# SCH_Juzer_pedal_sch_2024-03-11.net
KiCad netlist of a schematic drawn in EasyEDA
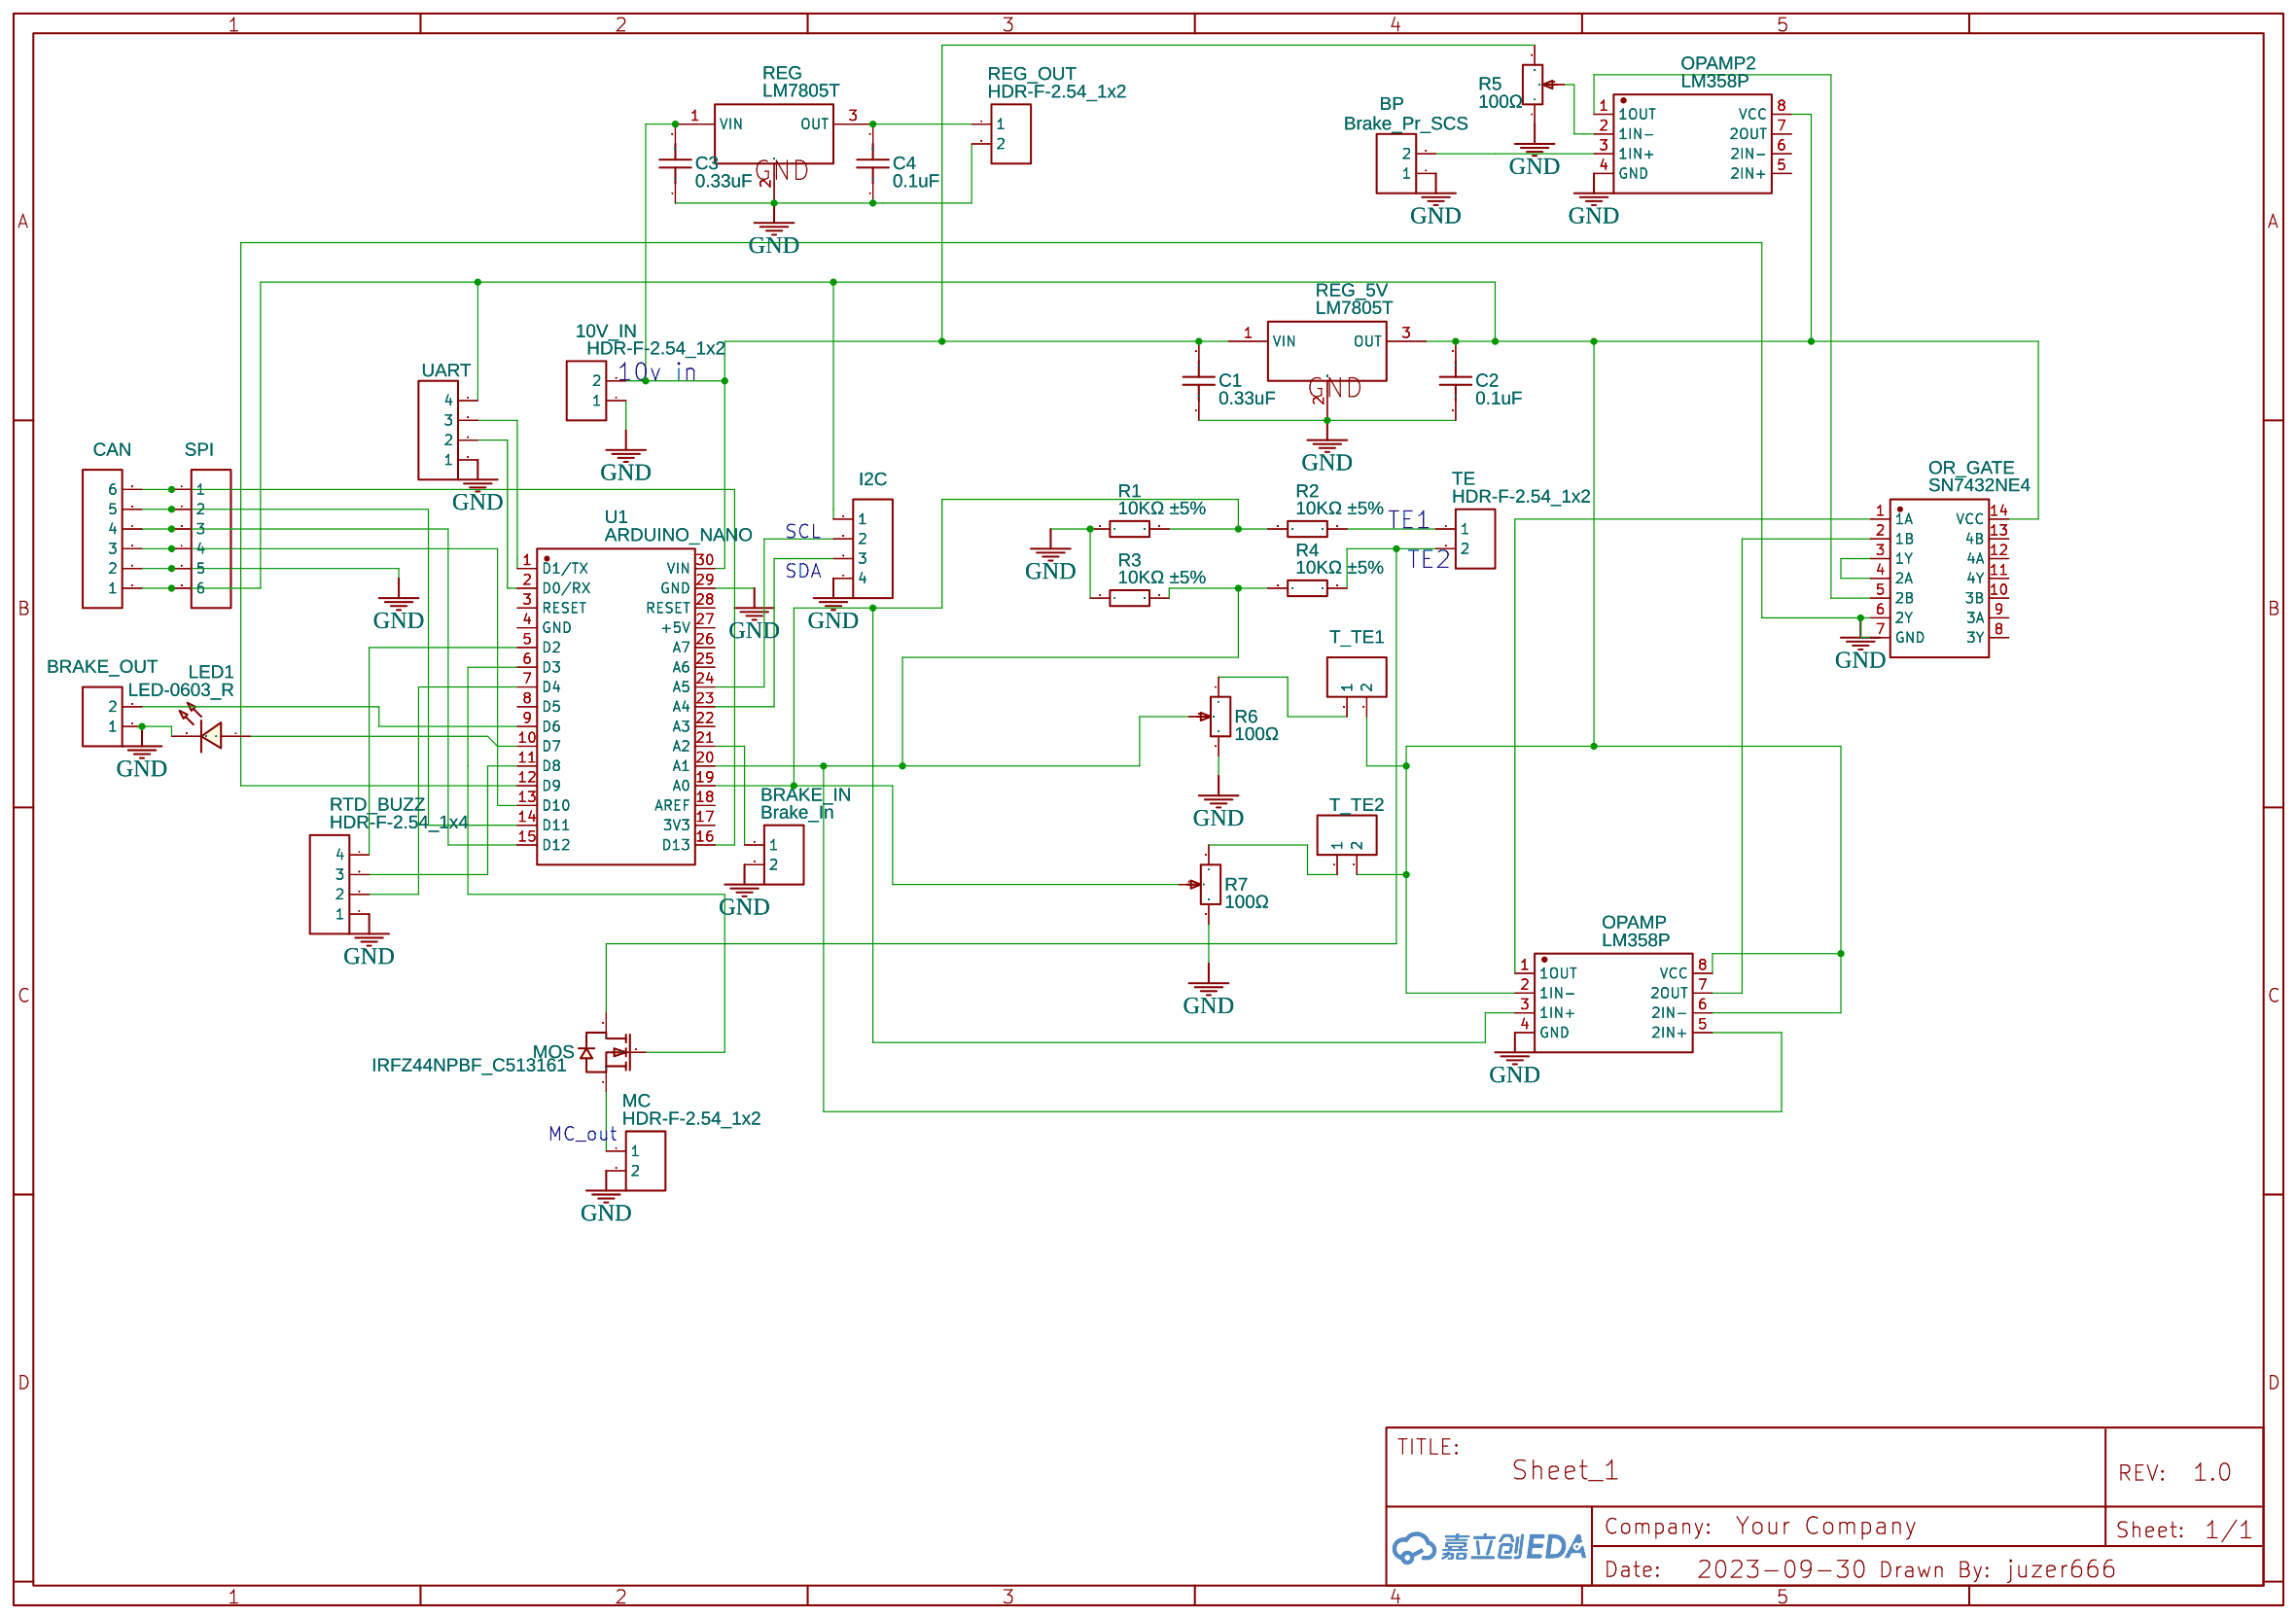
[diagram p0: schematic sheet]

(export (version "E")
  (design (tool "Eeschema 10.0.6"))
  (components
    (comp (ref "10V_IN") (value "HDR-F-2.54_1x2") (libsource (lib "") (part "HDR-F-2.54_1x2_3")))
    (comp (ref "BP") (value "Brake_Pr_SCS") (libsource (lib "") (part "HDR-F-2.54_1x2_2")))
    (comp (ref "BRAKE_IN") (value "Brake_In") (libsource (lib "") (part "HDR-F-2.54_1x2_6")))
    (comp (ref "BRAKE_OUT") (value "Brake_Out") (libsource (lib "") (part "HDR-F-2.54_1x2_4")))
    (comp (ref "C1")
      (value "0.33uF")
      (fields
        (field (name "Manufacturer Part") "250V 0.1UF 5% CBBCapacitor")
        (field (name "Manufacturer") "ReliaPro")
      )
      (libsource (lib "") (part "250V 0.1UF 5% CBBCapacitor"))
    )
    (comp (ref "C2")
      (value "0.1uF")
      (fields
        (field (name "Manufacturer Part") "250V 0.1UF 5% CBBCapacitor")
        (field (name "Manufacturer") "ReliaPro")
      )
      (libsource (lib "") (part "250V 0.1UF 5% CBBCapacitor"))
    )
    (comp (ref "C3")
      (value "0.33uF")
      (fields
        (field (name "Manufacturer Part") "250V 0.1UF 5% CBBCapacitor")
        (field (name "Manufacturer") "ReliaPro")
      )
      (libsource (lib "") (part "250V 0.1UF 5% CBBCapacitor"))
    )
    (comp (ref "C4")
      (value "0.1uF")
      (fields
        (field (name "Manufacturer Part") "250V 0.1UF 5% CBBCapacitor")
        (field (name "Manufacturer") "ReliaPro")
      )
      (libsource (lib "") (part "250V 0.1UF 5% CBBCapacitor"))
    )
    (comp (ref "CAN") (value "CAN") (libsource (lib "") (part "HDR-F-2.54_1x6_1")))
    (comp (ref "I2C") (value "I2C") (libsource (lib "") (part "HDR-F-2.54_1x4")))
    (comp (ref "LED1")
      (value "LED-0603_R")
      (fields
        (field (name "Manufacturer Part") "19-217/R6C-AL1M2VY/3T")
        (field (name "Manufacturer") "EVERLIGHT(台湾亿光)")
      )
      (libsource (lib "") (part "LED-0603_R"))
    )
    (comp (ref "MC") (value "HDR-F-2.54_1x2") (libsource (lib "") (part "HDR-F-2.54_1x2")))
    (comp (ref "MOS")
      (value "IRFZ44NPBF_C513161")
      (fields (field (name "Manufacturer Part") "IRFZ44NPBF"))
      (libsource (lib "") (part "IRFZ44NPBF_C513161"))
    )
    (comp (ref "OPAMP")
      (value "LM358P")
      (fields (field (name "Manufacturer") "TI(德州仪器)"))
      (libsource (lib "") (part "LM358P"))
    )
    (comp (ref "OPAMP2")
      (value "LM358P")
      (fields (field (name "Manufacturer") "TI(德州仪器)"))
      (libsource (lib "") (part "LM358P"))
    )
    (comp (ref "OR_GATE")
      (value "SN7432NE4")
      (fields (field (name "Manufacturer") "TI(德州仪器)"))
      (libsource (lib "") (part "SN7432NE4"))
    )
    (comp (ref "R1")
      (value "10KΩ ±5%")
      (fields
        (field (name "Manufacturer Part") "MF58 103J3470")
        (field (name "Manufacturer") "Nanjing Shiheng Elec")
      )
      (libsource (lib "") (part "RESISTANCE_10K"))
    )
    (comp (ref "R2")
      (value "10KΩ ±5%")
      (fields
        (field (name "Manufacturer Part") "MF58 103J3470")
        (field (name "Manufacturer") "Nanjing Shiheng Elec")
      )
      (libsource (lib "") (part "RESISTANCE_10K"))
    )
    (comp (ref "R3")
      (value "10KΩ ±5%")
      (fields
        (field (name "Manufacturer Part") "MF58 103J3470")
        (field (name "Manufacturer") "Nanjing Shiheng Elec")
      )
      (libsource (lib "") (part "RESISTANCE_10K"))
    )
    (comp (ref "R4")
      (value "10KΩ ±5%")
      (fields
        (field (name "Manufacturer Part") "MF58 103J3470")
        (field (name "Manufacturer") "Nanjing Shiheng Elec")
      )
      (libsource (lib "") (part "RESISTANCE_10K"))
    )
    (comp (ref "R5")
      (value "100Ω")
      (fields (field (name "Manufacturer Part") "3296W-1-101LF") (field (name "Manufacturer") "BOURNS"))
      (libsource (lib "") (part "3296W-1-101LF_1"))
    )
    (comp (ref "R6")
      (value "100Ω")
      (fields (field (name "Manufacturer Part") "3296W-1-101LF") (field (name "Manufacturer") "BOURNS"))
      (libsource (lib "") (part "3296W-1-101LF"))
    )
    (comp (ref "R7")
      (value "100Ω")
      (fields (field (name "Manufacturer Part") "3296W-1-101LF") (field (name "Manufacturer") "BOURNS"))
      (libsource (lib "") (part "3296W-1-101LF"))
    )
    (comp (ref "REG")
      (value "LM7805T")
      (fields (field (name "Manufacturer") "HGC(华冠)"))
      (libsource (lib "") (part "LM7805T_1"))
    )
    (comp (ref "REG_5V")
      (value "LM7805T")
      (fields (field (name "Manufacturer") "HGC(华冠)"))
      (libsource (lib "") (part "LM7805T"))
    )
    (comp (ref "REG_OUT") (value "HDR-F-2.54_1x2") (libsource (lib "") (part "HDR-F-2.54_1x2_1")))
    (comp (ref "RTD_BUZZ") (value "HDR-F-2.54_1x4") (libsource (lib "") (part "HDR-F-2.54_1x4_1")))
    (comp (ref "SPI") (value "SPI") (libsource (lib "") (part "HDR-F-2.54_1x6")))
    (comp (ref "TE") (value "HDR-F-2.54_1x2") (libsource (lib "") (part "HDR-F-2.54_1x2_7")))
    (comp (ref "T_TE1") (value "TE1_Test") (libsource (lib "") (part "HDR-F-2.54_1x2_5")))
    (comp (ref "T_TE2") (value "TE2_Test") (libsource (lib "") (part "HDR-F-2.54_1x2_5")))
    (comp (ref "U1") (value "ARDUINO_NANO") (libsource (lib "") (part "ARDUINO_NANO")))
    (comp (ref "UART") (value "UART") (libsource (lib "") (part "HDR-F-2.54_1x4_2")))
  )
  (nets
    (net (code "1") (name "GND") (class "Default")
      (node (ref "10V_IN") (pin "1") (pinfunction "1_1") (pintype "input"))
      (node (ref "BP") (pin "1") (pinfunction "1_1") (pintype "input"))
      (node (ref "BRAKE_IN") (pin "2") (pinfunction "2_2") (pintype "input"))
      (node (ref "BRAKE_OUT") (pin "1") (pinfunction "1_1") (pintype "input"))
      (node (ref "C1") (pin "1") (pinfunction "1_1") (pintype "unspecified"))
      (node (ref "C2") (pin "1") (pinfunction "1_1") (pintype "unspecified"))
      (node (ref "C3") (pin "1") (pinfunction "1_1") (pintype "unspecified"))
      (node (ref "C4") (pin "1") (pinfunction "1_1") (pintype "unspecified"))
      (node (ref "CAN") (pin "2") (pinfunction "2_2") (pintype "input"))
      (node (ref "I2C") (pin "4") (pinfunction "4_4") (pintype "unspecified"))
      (node (ref "LED1") (pin "2") (pinfunction "2_2") (pintype "unspecified"))
      (node (ref "MC") (pin "2") (pinfunction "2_2") (pintype "input"))
      (node (ref "OPAMP") (pin "4") (pinfunction "GND_4") (pintype "unspecified"))
      (node (ref "OPAMP2") (pin "4") (pinfunction "GND_4") (pintype "unspecified"))
      (node (ref "OR_GATE") (pin "6") (pinfunction "2Y_6") (pintype "unspecified"))
      (node (ref "OR_GATE") (pin "7") (pinfunction "GND_7") (pintype "unspecified"))
      (node (ref "R1") (pin "1") (pinfunction "1_1") (pintype "unspecified"))
      (node (ref "R3") (pin "1") (pinfunction "1_1") (pintype "unspecified"))
      (node (ref "R5") (pin "1") (pinfunction "1_1") (pintype "input"))
      (node (ref "R6") (pin "3") (pinfunction "3_3") (pintype "input"))
      (node (ref "R7") (pin "3") (pinfunction "3_3") (pintype "input"))
      (node (ref "REG") (pin "2") (pinfunction "GND_2") (pintype "passive"))
      (node (ref "REG_5V") (pin "2") (pinfunction "GND_2") (pintype "passive"))
      (node (ref "REG_OUT") (pin "2") (pinfunction "2_2") (pintype "input"))
      (node (ref "RTD_BUZZ") (pin "1") (pinfunction "1_1") (pintype "unspecified"))
      (node (ref "SPI") (pin "5") (pinfunction "5_5") (pintype "input"))
      (node (ref "U1") (pin "12") (pinfunction "D9_12") (pintype "unspecified"))
      (node (ref "U1") (pin "29") (pinfunction "GND_29") (pintype "unspecified"))
      (node (ref "UART") (pin "1") (pinfunction "1_1") (pintype "unspecified"))
    )
    (net (code "2") (name "Net-(MOS-D)") (class "Default")
      (node (ref "MOS") (pin "2") (pinfunction "D_2") (pintype "unspecified"))
      (node (ref "R4") (pin "2") (pinfunction "2_2") (pintype "unspecified"))
      (node (ref "TE") (pin "2") (pinfunction "2_2") (pintype "input"))
    )
    (net (code "3") (name "Net-(MOS-G)") (class "Default")
      (node (ref "MOS") (pin "1") (pinfunction "G_1") (pintype "unspecified"))
      (node (ref "U1") (pin "6") (pinfunction "D3_6") (pintype "unspecified"))
    )
    (net (code "4") (name "Net-(MOS-S)") (class "Default")
      (node (ref "MC") (pin "1") (pinfunction "1_1") (pintype "input"))
      (node (ref "MOS") (pin "3") (pinfunction "S_3") (pintype "unspecified"))
    )
    (net (code "5") (name "Net-(OPAMP-1IN+)") (class "Default")
      (node (ref "OPAMP") (pin "3") (pinfunction "1IN+_3") (pintype "unspecified"))
      (node (ref "R1") (pin "2") (pinfunction "2_2") (pintype "unspecified"))
      (node (ref "R2") (pin "1") (pinfunction "1_1") (pintype "unspecified"))
      (node (ref "R7") (pin "2") (pinfunction "2_2") (pintype "input"))
      (node (ref "U1") (pin "19") (pinfunction "A0_19") (pintype "unspecified"))
    )
    (net (code "6") (name "Net-(OPAMP-1IN-)") (class "Default")
      (node (ref "C2") (pin "2") (pinfunction "2_2") (pintype "unspecified"))
      (node (ref "CAN") (pin "1") (pinfunction "1_1") (pintype "input"))
      (node (ref "I2C") (pin "1") (pinfunction "1_1") (pintype "unspecified"))
      (node (ref "OPAMP") (pin "2") (pinfunction "1IN-_2") (pintype "unspecified"))
      (node (ref "OPAMP") (pin "6") (pinfunction "2IN-_6") (pintype "unspecified"))
      (node (ref "OPAMP") (pin "8") (pinfunction "VCC_8") (pintype "unspecified"))
      (node (ref "OPAMP2") (pin "8") (pinfunction "VCC_8") (pintype "unspecified"))
      (node (ref "OR_GATE") (pin "14") (pinfunction "VCC_14") (pintype "unspecified"))
      (node (ref "REG_5V") (pin "3") (pinfunction "OUT_3") (pintype "passive"))
      (node (ref "SPI") (pin "6") (pinfunction "6_6") (pintype "input"))
      (node (ref "T_TE1") (pin "2") (pinfunction "2_2") (pintype "input"))
      (node (ref "T_TE2") (pin "2") (pinfunction "2_2") (pintype "input"))
      (node (ref "UART") (pin "4") (pinfunction "4_4") (pintype "unspecified"))
    )
    (net (code "7") (name "Net-(OPAMP-1OUT)") (class "Default")
      (node (ref "OPAMP") (pin "1") (pinfunction "1OUT_1") (pintype "unspecified"))
      (node (ref "OR_GATE") (pin "1") (pinfunction "1A_1") (pintype "unspecified"))
    )
    (net (code "8") (name "Net-(OPAMP-2IN+)") (class "Default")
      (node (ref "OPAMP") (pin "5") (pinfunction "2IN+_5") (pintype "unspecified"))
      (node (ref "R3") (pin "2") (pinfunction "2_2") (pintype "unspecified"))
      (node (ref "R4") (pin "1") (pinfunction "1_1") (pintype "unspecified"))
      (node (ref "R6") (pin "2") (pinfunction "2_2") (pintype "input"))
      (node (ref "U1") (pin "20") (pinfunction "A1_20") (pintype "unspecified"))
    )
    (net (code "9") (name "Net-(OPAMP-2OUT)") (class "Default")
      (node (ref "OPAMP") (pin "7") (pinfunction "2OUT_7") (pintype "unspecified"))
      (node (ref "OR_GATE") (pin "2") (pinfunction "1B_2") (pintype "unspecified"))
    )
    (net (code "10") (name "Net-(OPAMP2-1IN+)") (class "Default")
      (node (ref "BP") (pin "2") (pinfunction "2_2") (pintype "input"))
      (node (ref "OPAMP2") (pin "3") (pinfunction "1IN+_3") (pintype "unspecified"))
    )
    (net (code "11") (name "Net-(OPAMP2-1IN-)") (class "Default")
      (node (ref "OPAMP2") (pin "2") (pinfunction "1IN-_2") (pintype "unspecified"))
      (node (ref "R5") (pin "2") (pinfunction "2_2") (pintype "input"))
    )
    (net (code "12") (name "Net-(OPAMP2-1OUT)") (class "Default")
      (node (ref "OPAMP2") (pin "1") (pinfunction "1OUT_1") (pintype "unspecified"))
      (node (ref "OR_GATE") (pin "5") (pinfunction "2B_5") (pintype "unspecified"))
    )
    (net (code "13") (name "Net-(OR_GATE-1Y)") (class "Default")
      (node (ref "OR_GATE") (pin "3") (pinfunction "1Y_3") (pintype "unspecified"))
      (node (ref "OR_GATE") (pin "4") (pinfunction "2A_4") (pintype "unspecified"))
    )
    (net (code "14") (name "Net-(R2-Pad2)") (class "Default")
      (node (ref "R2") (pin "2") (pinfunction "2_2") (pintype "unspecified"))
      (node (ref "TE") (pin "1") (pinfunction "1_1") (pintype "input"))
    )
    (net (code "15") (name "Net-(R6-Pad1)") (class "Default")
      (node (ref "R6") (pin "1") (pinfunction "1_1") (pintype "input"))
      (node (ref "T_TE1") (pin "1") (pinfunction "1_1") (pintype "input"))
    )
    (net (code "16") (name "Net-(R7-Pad1)") (class "Default")
      (node (ref "R7") (pin "1") (pinfunction "1_1") (pintype "input"))
      (node (ref "T_TE2") (pin "1") (pinfunction "1_1") (pintype "input"))
    )
    (net (code "17") (name "Net-(REG-OUT)") (class "Default")
      (node (ref "C4") (pin "2") (pinfunction "2_2") (pintype "unspecified"))
      (node (ref "REG") (pin "3") (pinfunction "OUT_3") (pintype "passive"))
      (node (ref "REG_OUT") (pin "1") (pinfunction "1_1") (pintype "input"))
    )
    (net (code "18") (name "Net-(REG-VIN)") (class "Default")
      (node (ref "10V_IN") (pin "2") (pinfunction "2_2") (pintype "input"))
      (node (ref "C1") (pin "2") (pinfunction "2_2") (pintype "unspecified"))
      (node (ref "C3") (pin "2") (pinfunction "2_2") (pintype "unspecified"))
      (node (ref "R5") (pin "3") (pinfunction "3_3") (pintype "input"))
      (node (ref "REG") (pin "1") (pinfunction "VIN_1") (pintype "passive"))
      (node (ref "REG_5V") (pin "1") (pinfunction "VIN_1") (pintype "passive"))
      (node (ref "U1") (pin "30") (pinfunction "VIN_30") (pintype "unspecified"))
    )
    (net (code "19") (name "Net-(U1-A2)") (class "Default")
      (node (ref "BRAKE_IN") (pin "1") (pinfunction "1_1") (pintype "input"))
      (node (ref "U1") (pin "21") (pinfunction "A2_21") (pintype "unspecified"))
    )
    (net (code "20") (name "Net-(U1-A4)") (class "Default")
      (node (ref "I2C") (pin "3") (pinfunction "3_3") (pintype "unspecified"))
      (node (ref "U1") (pin "23") (pinfunction "A4_23") (pintype "unspecified"))
    )
    (net (code "21") (name "Net-(U1-A5)") (class "Default")
      (node (ref "I2C") (pin "2") (pinfunction "2_2") (pintype "unspecified"))
      (node (ref "U1") (pin "24") (pinfunction "A5_24") (pintype "unspecified"))
    )
    (net (code "22") (name "Net-(U1-D0{slash}RX)") (class "Default")
      (node (ref "U1") (pin "2") (pinfunction "D0/RX_2") (pintype "unspecified"))
      (node (ref "UART") (pin "2") (pinfunction "2_2") (pintype "unspecified"))
    )
    (net (code "23") (name "Net-(U1-D1{slash}TX)") (class "Default")
      (node (ref "U1") (pin "1") (pinfunction "D1/TX_1") (pintype "unspecified"))
      (node (ref "UART") (pin "3") (pinfunction "3_3") (pintype "unspecified"))
    )
    (net (code "24") (name "Net-(U1-D2)") (class "Default")
      (node (ref "RTD_BUZZ") (pin "4") (pinfunction "4_4") (pintype "unspecified"))
      (node (ref "U1") (pin "5") (pinfunction "D2_5") (pintype "unspecified"))
    )
    (net (code "25") (name "Net-(U1-D4)") (class "Default")
      (node (ref "RTD_BUZZ") (pin "2") (pinfunction "2_2") (pintype "unspecified"))
      (node (ref "U1") (pin "7") (pinfunction "D4_7") (pintype "unspecified"))
    )
    (net (code "26") (name "Net-(U1-D6)") (class "Default")
      (node (ref "BRAKE_OUT") (pin "2") (pinfunction "2_2") (pintype "input"))
      (node (ref "U1") (pin "9") (pinfunction "D6_9") (pintype "unspecified"))
    )
    (net (code "27") (name "Net-(U1-D7)") (class "Default")
      (node (ref "LED1") (pin "1") (pinfunction "1_1") (pintype "unspecified"))
      (node (ref "U1") (pin "10") (pinfunction "D7_10") (pintype "unspecified"))
    )
    (net (code "28") (name "Net-(U1-D8)") (class "Default")
      (node (ref "RTD_BUZZ") (pin "3") (pinfunction "3_3") (pintype "unspecified"))
      (node (ref "U1") (pin "11") (pinfunction "D8_11") (pintype "unspecified"))
    )
    (net (code "29") (name "Net-(U1-D10)") (class "Default")
      (node (ref "CAN") (pin "3") (pinfunction "3_3") (pintype "input"))
      (node (ref "SPI") (pin "4") (pinfunction "4_4") (pintype "input"))
      (node (ref "U1") (pin "13") (pinfunction "D10_13") (pintype "unspecified"))
    )
    (net (code "30") (name "Net-(U1-D11)") (class "Default")
      (node (ref "CAN") (pin "5") (pinfunction "5_5") (pintype "input"))
      (node (ref "SPI") (pin "2") (pinfunction "2_2") (pintype "input"))
      (node (ref "U1") (pin "14") (pinfunction "D11_14") (pintype "unspecified"))
    )
    (net (code "31") (name "Net-(U1-D12)") (class "Default")
      (node (ref "CAN") (pin "4") (pinfunction "4_4") (pintype "input"))
      (node (ref "SPI") (pin "3") (pinfunction "3_3") (pintype "input"))
      (node (ref "U1") (pin "15") (pinfunction "D12_15") (pintype "unspecified"))
    )
    (net (code "32") (name "Net-(U1-D13)") (class "Default")
      (node (ref "CAN") (pin "6") (pinfunction "6_6") (pintype "input"))
      (node (ref "SPI") (pin "1") (pinfunction "1_1") (pintype "input"))
      (node (ref "U1") (pin "16") (pinfunction "D13_16") (pintype "unspecified"))
    )
    (net (code "33") (name "unconnected-(OPAMP2-2IN+-Pad5)") (class "Default")
      (node (ref "OPAMP2") (pin "5") (pinfunction "2IN+_5") (pintype "unspecified"))
    )
    (net (code "34") (name "unconnected-(OPAMP2-2IN--Pad6)") (class "Default")
      (node (ref "OPAMP2") (pin "6") (pinfunction "2IN-_6") (pintype "unspecified"))
    )
    (net (code "35") (name "unconnected-(OPAMP2-2OUT-Pad7)") (class "Default")
      (node (ref "OPAMP2") (pin "7") (pinfunction "2OUT_7") (pintype "unspecified"))
    )
    (net (code "36") (name "unconnected-(OR_GATE-3A-Pad9)") (class "Default")
      (node (ref "OR_GATE") (pin "9") (pinfunction "3A_9") (pintype "unspecified"))
    )
    (net (code "37") (name "unconnected-(OR_GATE-3B-Pad10)") (class "Default")
      (node (ref "OR_GATE") (pin "10") (pinfunction "3B_10") (pintype "unspecified"))
    )
    (net (code "38") (name "unconnected-(OR_GATE-3Y-Pad8)") (class "Default")
      (node (ref "OR_GATE") (pin "8") (pinfunction "3Y_8") (pintype "unspecified"))
    )
    (net (code "39") (name "unconnected-(OR_GATE-4A-Pad12)") (class "Default")
      (node (ref "OR_GATE") (pin "12") (pinfunction "4A_12") (pintype "unspecified"))
    )
    (net (code "40") (name "unconnected-(OR_GATE-4B-Pad13)") (class "Default")
      (node (ref "OR_GATE") (pin "13") (pinfunction "4B_13") (pintype "unspecified"))
    )
    (net (code "41") (name "unconnected-(OR_GATE-4Y-Pad11)") (class "Default")
      (node (ref "OR_GATE") (pin "11") (pinfunction "4Y_11") (pintype "unspecified"))
    )
    (net (code "42") (name "unconnected-(U1-+5V-Pad27)") (class "Default")
      (node (ref "U1") (pin "27") (pinfunction "+5V_27") (pintype "unspecified"))
    )
    (net (code "43") (name "unconnected-(U1-3V3-Pad17)") (class "Default")
      (node (ref "U1") (pin "17") (pinfunction "3V3_17") (pintype "unspecified"))
    )
    (net (code "44") (name "unconnected-(U1-A3-Pad22)") (class "Default")
      (node (ref "U1") (pin "22") (pinfunction "A3_22") (pintype "unspecified"))
    )
    (net (code "45") (name "unconnected-(U1-A6-Pad25)") (class "Default")
      (node (ref "U1") (pin "25") (pinfunction "A6_25") (pintype "unspecified"))
    )
    (net (code "46") (name "unconnected-(U1-A7-Pad26)") (class "Default")
      (node (ref "U1") (pin "26") (pinfunction "A7_26") (pintype "unspecified"))
    )
    (net (code "47") (name "unconnected-(U1-AREF-Pad18)") (class "Default")
      (node (ref "U1") (pin "18") (pinfunction "AREF_18") (pintype "unspecified"))
    )
    (net (code "48") (name "unconnected-(U1-D5-Pad8)") (class "Default")
      (node (ref "U1") (pin "8") (pinfunction "D5_8") (pintype "unspecified"))
    )
    (net (code "49") (name "unconnected-(U1-GND-Pad4)") (class "Default")
      (node (ref "U1") (pin "4") (pinfunction "GND_4") (pintype "unspecified"))
    )
    (net (code "50") (name "unconnected-(U1-RESET-Pad3)") (class "Default")
      (node (ref "U1") (pin "3") (pinfunction "RESET_3") (pintype "unspecified"))
    )
    (net (code "51") (name "unconnected-(U1-RESET-Pad28)") (class "Default")
      (node (ref "U1") (pin "28") (pinfunction "RESET_28") (pintype "unspecified"))
    )
  )
)
